# myPowerNode.net
KiCad netlist of a schematic drawn in EAGLE
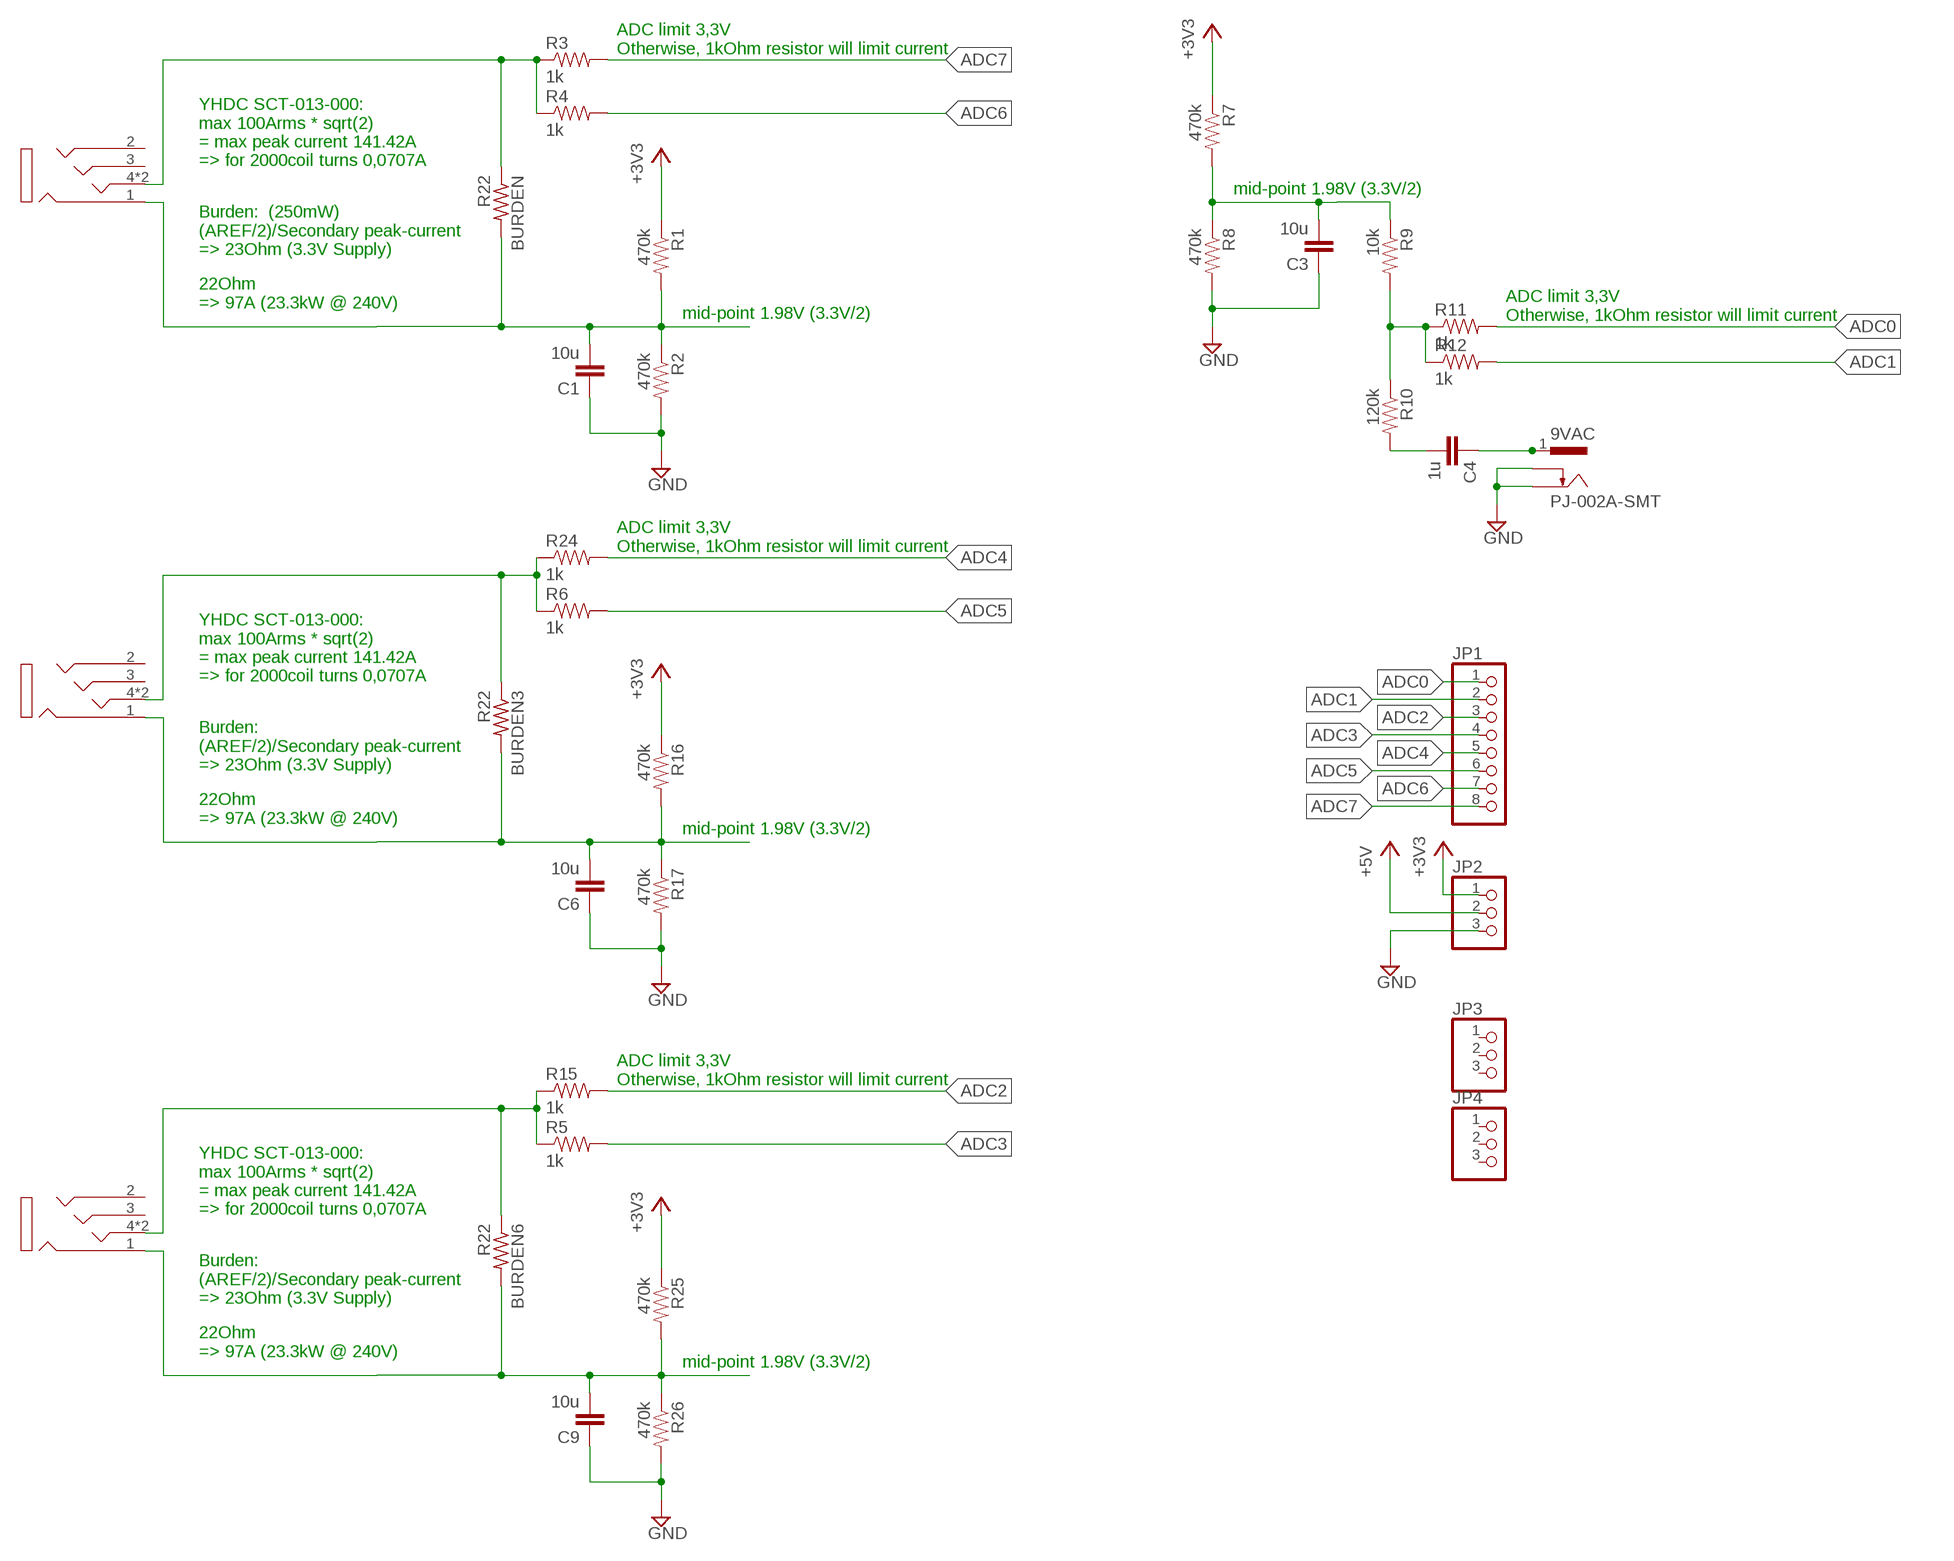
[diagram p0: schematic, sheet 1]

(export (version "E")
  (design (tool "Eeschema 10.0.6"))
  (components
    (comp (ref "9VAC")
      (value "PJ-002A-SMT")
      (footprint "eagle-import:CUI_PJ-002B-SMT")
      (libsource (lib "eagle-import") (part "PJ-002A-SMT"))
    )
    (comp (ref "BURDEN")
      (value "R22")
      (footprint "eagle-import:R0805")
      (libsource (lib "eagle-import") (part "R-US_R0805"))
    )
    (comp (ref "BURDEN3")
      (value "R22")
      (footprint "eagle-import:R0805")
      (libsource (lib "eagle-import") (part "R-US_R0805"))
    )
    (comp (ref "BURDEN6")
      (value "R22")
      (footprint "eagle-import:R0805")
      (libsource (lib "eagle-import") (part "R-US_R0805"))
    )
    (comp (ref "C1")
      (value "10u")
      (footprint "eagle-import:0603-CAP")
      (libsource (lib "eagle-import") (part "CAP0603-CAP"))
    )
    (comp (ref "C3")
      (value "10u")
      (footprint "eagle-import:0603-CAP")
      (libsource (lib "eagle-import") (part "CAP0603-CAP"))
    )
    (comp (ref "C4")
      (value "1u")
      (footprint "eagle-import:0603-CAP")
      (libsource (lib "eagle-import") (part "CAP0603-CAP"))
    )
    (comp (ref "C6")
      (value "10u")
      (footprint "eagle-import:0603-CAP")
      (libsource (lib "eagle-import") (part "CAP0603-CAP"))
    )
    (comp (ref "C9")
      (value "10u")
      (footprint "eagle-import:0603-CAP")
      (libsource (lib "eagle-import") (part "CAP0603-CAP"))
    )
    (comp (ref "CT1")
      (value "1503_13")
      (footprint "eagle-import:1503-03")
      (libsource (lib "eagle-import") (part "1503_13"))
    )
    (comp (ref "CT4")
      (value "1503_13")
      (footprint "eagle-import:1503-03")
      (libsource (lib "eagle-import") (part "1503_13"))
    )
    (comp (ref "CT7")
      (value "1503_13")
      (footprint "eagle-import:1503-03")
      (libsource (lib "eagle-import") (part "1503_13"))
    )
    (comp (ref "JP1")
      (value "PINHD-1X8CLEANBIG")
      (footprint "eagle-import:1X08-CLEANBIG")
      (libsource (lib "eagle-import") (part "PINHD-1X8CLEANBIG"))
    )
    (comp (ref "JP2")
      (value "PINHD-1X3CB")
      (footprint "eagle-import:1X03-CLEANBIG")
      (libsource (lib "eagle-import") (part "PINHD-1X3CB"))
    )
    (comp (ref "JP3")
      (value "PINHD-1X3CB")
      (footprint "eagle-import:1X03-CLEANBIG")
      (libsource (lib "eagle-import") (part "PINHD-1X3CB"))
    )
    (comp (ref "JP4")
      (value "PINHD-1X3CB")
      (footprint "eagle-import:1X03-CLEANBIG")
      (libsource (lib "eagle-import") (part "PINHD-1X3CB"))
    )
    (comp (ref "R1")
      (value "470k")
      (footprint "eagle-import:0603-RES")
      (libsource (lib "eagle-import") (part "RESISTOR0603-RES"))
    )
    (comp (ref "R2")
      (value "470k")
      (footprint "eagle-import:0603-RES")
      (libsource (lib "eagle-import") (part "RESISTOR0603-RES"))
    )
    (comp (ref "R3")
      (value "1k")
      (footprint "eagle-import:0603-RES")
      (libsource (lib "eagle-import") (part "RESISTOR0603-RES"))
    )
    (comp (ref "R4")
      (value "1k")
      (footprint "eagle-import:0603-RES")
      (libsource (lib "eagle-import") (part "RESISTOR0603-RES"))
    )
    (comp (ref "R5")
      (value "1k")
      (footprint "eagle-import:0603-RES")
      (libsource (lib "eagle-import") (part "RESISTOR0603-RES"))
    )
    (comp (ref "R6")
      (value "1k")
      (footprint "eagle-import:0603-RES")
      (libsource (lib "eagle-import") (part "RESISTOR0603-RES"))
    )
    (comp (ref "R7")
      (value "470k")
      (footprint "eagle-import:0603-RES")
      (libsource (lib "eagle-import") (part "RESISTOR0603-RES"))
    )
    (comp (ref "R8")
      (value "470k")
      (footprint "eagle-import:0603-RES")
      (libsource (lib "eagle-import") (part "RESISTOR0603-RES"))
    )
    (comp (ref "R9")
      (value "10k")
      (footprint "eagle-import:0603-RES")
      (libsource (lib "eagle-import") (part "RESISTOR0603-RES"))
    )
    (comp (ref "R10")
      (value "120k")
      (footprint "eagle-import:0603-RES")
      (libsource (lib "eagle-import") (part "RESISTOR0603-RES"))
    )
    (comp (ref "R11")
      (value "1k")
      (footprint "eagle-import:0603-RES")
      (libsource (lib "eagle-import") (part "RESISTOR0603-RES"))
    )
    (comp (ref "R12")
      (value "1k")
      (footprint "eagle-import:0603-RES")
      (libsource (lib "eagle-import") (part "RESISTOR0603-RES"))
    )
    (comp (ref "R15")
      (value "1k")
      (footprint "eagle-import:0603-RES")
      (libsource (lib "eagle-import") (part "RESISTOR0603-RES"))
    )
    (comp (ref "R16")
      (value "470k")
      (footprint "eagle-import:0603-RES")
      (libsource (lib "eagle-import") (part "RESISTOR0603-RES"))
    )
    (comp (ref "R17")
      (value "470k")
      (footprint "eagle-import:0603-RES")
      (libsource (lib "eagle-import") (part "RESISTOR0603-RES"))
    )
    (comp (ref "R24")
      (value "1k")
      (footprint "eagle-import:0603-RES")
      (libsource (lib "eagle-import") (part "RESISTOR0603-RES"))
    )
    (comp (ref "R25")
      (value "470k")
      (footprint "eagle-import:0603-RES")
      (libsource (lib "eagle-import") (part "RESISTOR0603-RES"))
    )
    (comp (ref "R26")
      (value "470k")
      (footprint "eagle-import:0603-RES")
      (libsource (lib "eagle-import") (part "RESISTOR0603-RES"))
    )
  )
  (nets
    (net (code "1") (name "+3V3") (class "Default")
      (node (ref "JP2") (pin "1") (pinfunction "1_1") (pintype "passive"))
      (node (ref "R1") (pin "1") (pinfunction "1_1") (pintype "passive"))
      (node (ref "R16") (pin "1") (pinfunction "1_1") (pintype "passive"))
      (node (ref "R25") (pin "1") (pinfunction "1_1") (pintype "passive"))
      (node (ref "R7") (pin "1") (pinfunction "1_1") (pintype "passive"))
    )
    (net (code "2") (name "+5V") (class "Default")
      (node (ref "JP2") (pin "2") (pinfunction "2_2") (pintype "passive"))
    )
    (net (code "3") (name "ADC0") (class "Default")
      (node (ref "JP1") (pin "1") (pinfunction "1_1") (pintype "passive"))
      (node (ref "R11") (pin "2") (pinfunction "2_2") (pintype "passive"))
    )
    (net (code "4") (name "ADC1") (class "Default")
      (node (ref "JP1") (pin "2") (pinfunction "2_2") (pintype "passive"))
      (node (ref "R12") (pin "2") (pinfunction "2_2") (pintype "passive"))
    )
    (net (code "5") (name "ADC2") (class "Default")
      (node (ref "JP1") (pin "3") (pinfunction "3_3") (pintype "passive"))
      (node (ref "R15") (pin "2") (pinfunction "2_2") (pintype "passive"))
    )
    (net (code "6") (name "ADC3") (class "Default")
      (node (ref "JP1") (pin "4") (pinfunction "4_4") (pintype "passive"))
      (node (ref "R5") (pin "2") (pinfunction "2_2") (pintype "passive"))
    )
    (net (code "7") (name "ADC4") (class "Default")
      (node (ref "JP1") (pin "5") (pinfunction "5_5") (pintype "passive"))
      (node (ref "R24") (pin "2") (pinfunction "2_2") (pintype "passive"))
    )
    (net (code "8") (name "ADC5") (class "Default")
      (node (ref "JP1") (pin "6") (pinfunction "6_6") (pintype "passive"))
      (node (ref "R6") (pin "2") (pinfunction "2_2") (pintype "passive"))
    )
    (net (code "9") (name "ADC6") (class "Default")
      (node (ref "JP1") (pin "7") (pinfunction "7_7") (pintype "passive"))
      (node (ref "R4") (pin "2") (pinfunction "2_2") (pintype "passive"))
    )
    (net (code "10") (name "ADC7") (class "Default")
      (node (ref "JP1") (pin "8") (pinfunction "8_8") (pintype "passive"))
      (node (ref "R3") (pin "2") (pinfunction "2_2") (pintype "passive"))
    )
    (net (code "11") (name "GND") (class "Default")
      (node (ref "9VAC") (pin "3") (pinfunction "3_3") (pintype "passive"))
      (node (ref "9VAC") (pin "4") (pinfunction "4_4") (pintype "passive"))
      (node (ref "C1") (pin "1") (pinfunction "1_1") (pintype "passive"))
      (node (ref "C3") (pin "1") (pinfunction "1_1") (pintype "passive"))
      (node (ref "C6") (pin "1") (pinfunction "1_1") (pintype "passive"))
      (node (ref "C9") (pin "1") (pinfunction "1_1") (pintype "passive"))
      (node (ref "JP2") (pin "3") (pinfunction "3_3") (pintype "passive"))
      (node (ref "R17") (pin "2") (pinfunction "2_2") (pintype "passive"))
      (node (ref "R2") (pin "2") (pinfunction "2_2") (pintype "passive"))
      (node (ref "R26") (pin "2") (pinfunction "2_2") (pintype "passive"))
      (node (ref "R8") (pin "2") (pinfunction "2_2") (pintype "passive"))
    )
    (net (code "12") (name "Net-(9VAC-Pad1)") (class "Default")
      (node (ref "9VAC") (pin "1") (pinfunction "1_1") (pintype "passive"))
      (node (ref "9VAC") (pin "2") (pinfunction "2_2") (pintype "passive"))
      (node (ref "C4") (pin "1") (pinfunction "1_1") (pintype "passive"))
    )
    (net (code "13") (name "Net-(BURDEN-Pad1)") (class "Default")
      (node (ref "BURDEN") (pin "1") (pinfunction "1_1") (pintype "passive"))
      (node (ref "CT1") (pin "4") (pinfunction "4_4") (pintype "bidirectional"))
      (node (ref "CT1") (pin "4-2") (pinfunction "4_4-2") (pintype "bidirectional"))
      (node (ref "R3") (pin "1") (pinfunction "1_1") (pintype "passive"))
      (node (ref "R4") (pin "1") (pinfunction "1_1") (pintype "passive"))
    )
    (net (code "14") (name "Net-(BURDEN-Pad2)") (class "Default")
      (node (ref "BURDEN") (pin "2") (pinfunction "2_2") (pintype "passive"))
      (node (ref "C1") (pin "2") (pinfunction "2_2") (pintype "passive"))
      (node (ref "CT1") (pin "1") (pinfunction "1_1") (pintype "bidirectional"))
      (node (ref "R1") (pin "2") (pinfunction "2_2") (pintype "passive"))
      (node (ref "R2") (pin "1") (pinfunction "1_1") (pintype "passive"))
    )
    (net (code "15") (name "Net-(BURDEN3-Pad1)") (class "Default")
      (node (ref "BURDEN3") (pin "1") (pinfunction "1_1") (pintype "passive"))
      (node (ref "CT4") (pin "4") (pinfunction "4_4") (pintype "bidirectional"))
      (node (ref "CT4") (pin "4-2") (pinfunction "4_4-2") (pintype "bidirectional"))
      (node (ref "R24") (pin "1") (pinfunction "1_1") (pintype "passive"))
      (node (ref "R6") (pin "1") (pinfunction "1_1") (pintype "passive"))
    )
    (net (code "16") (name "Net-(BURDEN3-Pad2)") (class "Default")
      (node (ref "BURDEN3") (pin "2") (pinfunction "2_2") (pintype "passive"))
      (node (ref "C6") (pin "2") (pinfunction "2_2") (pintype "passive"))
      (node (ref "CT4") (pin "1") (pinfunction "1_1") (pintype "bidirectional"))
      (node (ref "R16") (pin "2") (pinfunction "2_2") (pintype "passive"))
      (node (ref "R17") (pin "1") (pinfunction "1_1") (pintype "passive"))
    )
    (net (code "17") (name "Net-(BURDEN6-Pad1)") (class "Default")
      (node (ref "BURDEN6") (pin "1") (pinfunction "1_1") (pintype "passive"))
      (node (ref "CT7") (pin "4") (pinfunction "4_4") (pintype "bidirectional"))
      (node (ref "CT7") (pin "4-2") (pinfunction "4_4-2") (pintype "bidirectional"))
      (node (ref "R15") (pin "1") (pinfunction "1_1") (pintype "passive"))
      (node (ref "R5") (pin "1") (pinfunction "1_1") (pintype "passive"))
    )
    (net (code "18") (name "Net-(BURDEN6-Pad2)") (class "Default")
      (node (ref "BURDEN6") (pin "2") (pinfunction "2_2") (pintype "passive"))
      (node (ref "C9") (pin "2") (pinfunction "2_2") (pintype "passive"))
      (node (ref "CT7") (pin "1") (pinfunction "1_1") (pintype "bidirectional"))
      (node (ref "R25") (pin "2") (pinfunction "2_2") (pintype "passive"))
      (node (ref "R26") (pin "1") (pinfunction "1_1") (pintype "passive"))
    )
    (net (code "19") (name "Net-(C3-Pad2)") (class "Default")
      (node (ref "C3") (pin "2") (pinfunction "2_2") (pintype "passive"))
      (node (ref "R7") (pin "2") (pinfunction "2_2") (pintype "passive"))
      (node (ref "R8") (pin "1") (pinfunction "1_1") (pintype "passive"))
      (node (ref "R9") (pin "1") (pinfunction "1_1") (pintype "passive"))
    )
    (net (code "20") (name "Net-(C4-Pad2)") (class "Default")
      (node (ref "C4") (pin "2") (pinfunction "2_2") (pintype "passive"))
      (node (ref "R10") (pin "2") (pinfunction "2_2") (pintype "passive"))
    )
    (net (code "21") (name "Net-(R10-Pad1)") (class "Default")
      (node (ref "R10") (pin "1") (pinfunction "1_1") (pintype "passive"))
      (node (ref "R11") (pin "1") (pinfunction "1_1") (pintype "passive"))
      (node (ref "R12") (pin "1") (pinfunction "1_1") (pintype "passive"))
      (node (ref "R9") (pin "2") (pinfunction "2_2") (pintype "passive"))
    )
    (net (code "22") (name "unconnected-(CT1-Pad2)") (class "Default")
      (node (ref "CT1") (pin "2") (pinfunction "2_2") (pintype "bidirectional"))
    )
    (net (code "23") (name "unconnected-(CT1-Pad3)") (class "Default")
      (node (ref "CT1") (pin "3") (pinfunction "3_3") (pintype "bidirectional"))
    )
    (net (code "24") (name "unconnected-(CT4-Pad2)") (class "Default")
      (node (ref "CT4") (pin "2") (pinfunction "2_2") (pintype "bidirectional"))
    )
    (net (code "25") (name "unconnected-(CT4-Pad3)") (class "Default")
      (node (ref "CT4") (pin "3") (pinfunction "3_3") (pintype "bidirectional"))
    )
    (net (code "26") (name "unconnected-(CT7-Pad2)") (class "Default")
      (node (ref "CT7") (pin "2") (pinfunction "2_2") (pintype "bidirectional"))
    )
    (net (code "27") (name "unconnected-(CT7-Pad3)") (class "Default")
      (node (ref "CT7") (pin "3") (pinfunction "3_3") (pintype "bidirectional"))
    )
    (net (code "28") (name "unconnected-(JP3-Pad1)") (class "Default")
      (node (ref "JP3") (pin "1") (pinfunction "1_1") (pintype "passive"))
    )
    (net (code "29") (name "unconnected-(JP3-Pad2)") (class "Default")
      (node (ref "JP3") (pin "2") (pinfunction "2_2") (pintype "passive"))
    )
    (net (code "30") (name "unconnected-(JP3-Pad3)") (class "Default")
      (node (ref "JP3") (pin "3") (pinfunction "3_3") (pintype "passive"))
    )
    (net (code "31") (name "unconnected-(JP4-Pad1)") (class "Default")
      (node (ref "JP4") (pin "1") (pinfunction "1_1") (pintype "passive"))
    )
    (net (code "32") (name "unconnected-(JP4-Pad2)") (class "Default")
      (node (ref "JP4") (pin "2") (pinfunction "2_2") (pintype "passive"))
    )
    (net (code "33") (name "unconnected-(JP4-Pad3)") (class "Default")
      (node (ref "JP4") (pin "3") (pinfunction "3_3") (pintype "passive"))
    )
  )
)
